# 04_CONNECTOR_IN.net
KiCad netlist of a schematic drawn in Altium Designer
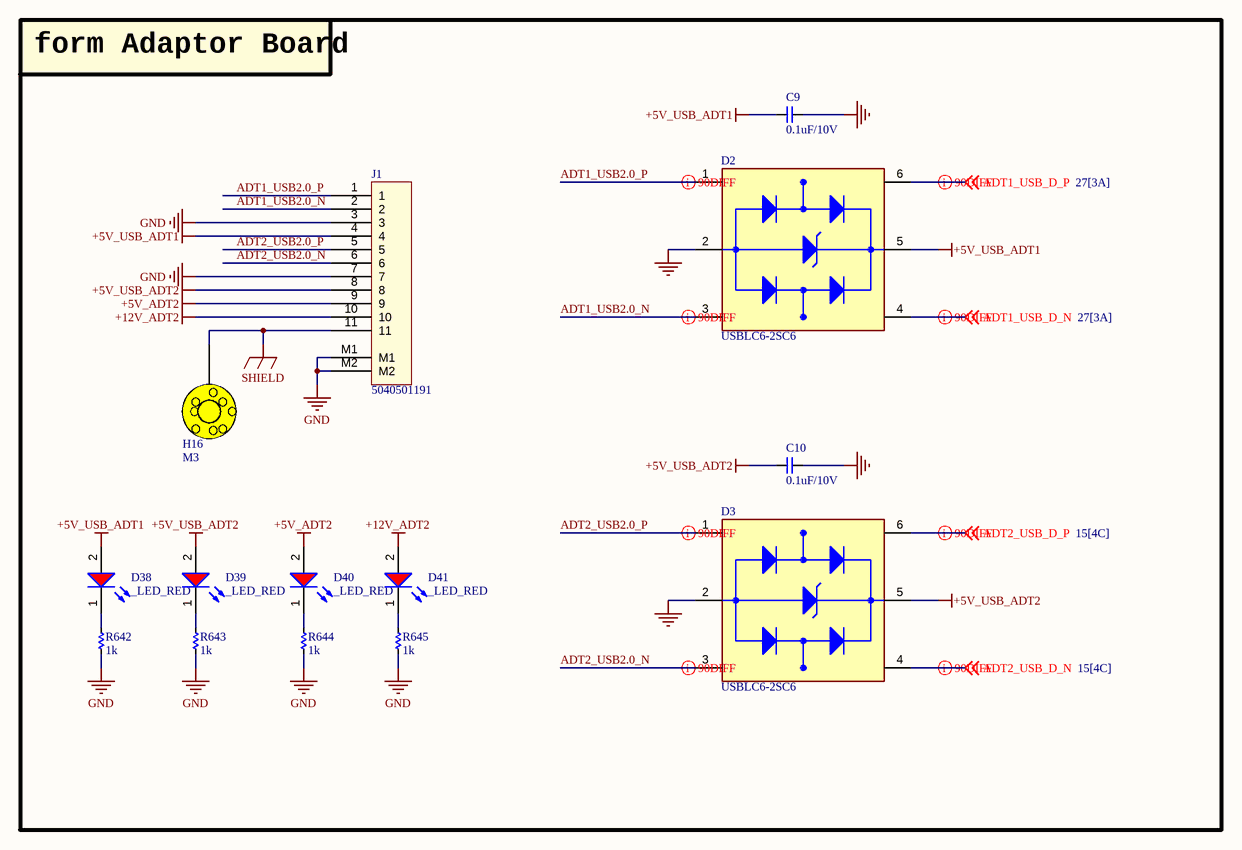
[diagram p0: 04_CONNECTOR_IN.SchDoc]

(export (version "E")
  (design (tool "Eeschema 10.0.6"))
  (components
    (comp (ref "C9")
      (value "0.1uF/10V")
      (footprint "CAP_C_1005X60")
      (description "CAP CHIP")
      (libsource (lib "LABLIB") (part "_CAP_C_2"))
    )
    (comp (ref "C10")
      (value "0.1uF/10V")
      (footprint "CAP_C_1005X60")
      (description "CAP CHIP")
      (libsource (lib "LABLIB") (part "_CAP_C_2"))
    )
    (comp (ref "D2")
      (value "USBLC6-2SC6")
      (footprint "SOT95P280X145-6N")
      (description "17V Clamp 5A (8/20Âµs) Ipp Tvs Diode Surface Mount SOT-23-6")
      (fields (field (name "MF") "STMicroelectronics"))
      (libsource (lib "USBLC6-2SC6") (part "USBLC6-2SC6"))
    )
    (comp (ref "D3")
      (value "USBLC6-2SC6")
      (footprint "SOT95P280X145-6N")
      (description "17V Clamp 5A (8/20Âµs) Ipp Tvs Diode Surface Mount SOT-23-6")
      (fields (field (name "MF") "STMicroelectronics"))
      (libsource (lib "USBLC6-2SC6") (part "USBLC6-2SC6"))
    )
    (comp (ref "D38") (value "_LED_RED") (footprint "LED_0603") (libsource (lib "LABLIB") (part "_LED_RED")))
    (comp (ref "D39") (value "_LED_RED") (footprint "LED_0603") (libsource (lib "LABLIB") (part "_LED_RED")))
    (comp (ref "D40") (value "_LED_RED") (footprint "LED_0603") (libsource (lib "LABLIB") (part "_LED_RED")))
    (comp (ref "D41") (value "_LED_RED") (footprint "LED_0603") (libsource (lib "LABLIB") (part "_LED_RED")))
    (comp (ref "H16")
      (value "M3")
      (footprint "Testpoint_TH_D350H250")
      (libsource (lib "hex_M3") (part "HEX-M3"))
    )
    (comp (ref "J1")
      (value "5040501191")
      (footprint "MOLEX_5040501191")
      (libsource (lib "LABLIB") (part "Header 11x1_2M"))
    )
    (comp (ref "R642")
      (value "1k")
      (footprint "RES_C_1005X40")
      (description "RES")
      (libsource (lib "LABLIB") (part "_RES_B_2"))
    )
    (comp (ref "R643")
      (value "1k")
      (footprint "RES_C_1005X40")
      (description "RES")
      (libsource (lib "LABLIB") (part "_RES_B_2"))
    )
    (comp (ref "R644")
      (value "1k")
      (footprint "RES_C_1005X40")
      (description "RES")
      (libsource (lib "LABLIB") (part "_RES_B_2"))
    )
    (comp (ref "R645")
      (value "1k")
      (footprint "RES_C_1005X40")
      (description "RES")
      (libsource (lib "LABLIB") (part "_RES_B_2"))
    )
  )
  (nets
    (net (code "1") (name "+5V_ADT2") (class "Default")
      (node (ref "D40") (pin "2") (pinfunction "A_2") (pintype "passive"))
      (node (ref "J1") (pin "9") (pinfunction "9_9") (pintype "passive"))
    )
    (net (code "2") (name "+5V_USB_ADT1") (class "Default")
      (node (ref "C9") (pin "2") (pinfunction "2_2") (pintype "passive"))
      (node (ref "D2") (pin "5") (pinfunction "VBUS_5") (pintype "power_in"))
      (node (ref "D38") (pin "2") (pinfunction "A_2") (pintype "passive"))
      (node (ref "J1") (pin "4") (pinfunction "4_4") (pintype "passive"))
    )
    (net (code "3") (name "+5V_USB_ADT2") (class "Default")
      (node (ref "C10") (pin "2") (pinfunction "2_2") (pintype "passive"))
      (node (ref "D3") (pin "5") (pinfunction "VBUS_5") (pintype "power_in"))
      (node (ref "D39") (pin "2") (pinfunction "A_2") (pintype "passive"))
      (node (ref "J1") (pin "8") (pinfunction "8_8") (pintype "passive"))
    )
    (net (code "4") (name "+12V_ADT2") (class "Default")
      (node (ref "D41") (pin "2") (pinfunction "A_2") (pintype "passive"))
      (node (ref "J1") (pin "10") (pinfunction "10_10") (pintype "passive"))
    )
    (net (code "5") (name "/ADT1_USB2.0_N") (class "Default")
      (node (ref "D2") (pin "3") (pinfunction "I/O2_IN_3") (pintype "passive"))
      (node (ref "J1") (pin "2") (pinfunction "2_2") (pintype "passive"))
    )
    (net (code "6") (name "/ADT1_USB2.0_P") (class "Default")
      (node (ref "D2") (pin "1") (pinfunction "I/O1_IN_1") (pintype "passive"))
      (node (ref "J1") (pin "1") (pinfunction "1_1") (pintype "passive"))
    )
    (net (code "7") (name "/ADT2_USB2.0_N") (class "Default")
      (node (ref "D3") (pin "3") (pinfunction "I/O2_IN_3") (pintype "passive"))
      (node (ref "J1") (pin "6") (pinfunction "6_6") (pintype "passive"))
    )
    (net (code "8") (name "/ADT2_USB2.0_P") (class "Default")
      (node (ref "D3") (pin "1") (pinfunction "I/O1_IN_1") (pintype "passive"))
      (node (ref "J1") (pin "5") (pinfunction "5_5") (pintype "passive"))
    )
    (net (code "9") (name "ADT1_USB_D_N") (class "Default")
      (node (ref "D2") (pin "4") (pinfunction "I/O2_OUT_4") (pintype "passive"))
    )
    (net (code "10") (name "ADT1_USB_D_P") (class "Default")
      (node (ref "D2") (pin "6") (pinfunction "I/O1_OUT_6") (pintype "passive"))
    )
    (net (code "11") (name "ADT2_USB_D_N") (class "Default")
      (node (ref "D3") (pin "4") (pinfunction "I/O2_OUT_4") (pintype "passive"))
    )
    (net (code "12") (name "ADT2_USB_D_P") (class "Default")
      (node (ref "D3") (pin "6") (pinfunction "I/O1_OUT_6") (pintype "passive"))
    )
    (net (code "13") (name "GND") (class "Default")
      (node (ref "C10") (pin "1") (pinfunction "1_1") (pintype "passive"))
      (node (ref "C9") (pin "1") (pinfunction "1_1") (pintype "passive"))
      (node (ref "D2") (pin "2") (pinfunction "GND_2") (pintype "power_in"))
      (node (ref "D3") (pin "2") (pinfunction "GND_2") (pintype "power_in"))
      (node (ref "J1") (pin "3") (pinfunction "3_3") (pintype "passive"))
      (node (ref "J1") (pin "7") (pinfunction "7_7") (pintype "passive"))
      (node (ref "J1") (pin "M1") (pinfunction "M1_M1") (pintype "passive"))
      (node (ref "J1") (pin "M2") (pinfunction "M2_M2") (pintype "passive"))
      (node (ref "R642") (pin "1") (pinfunction "1_1") (pintype "passive"))
      (node (ref "R643") (pin "1") (pinfunction "1_1") (pintype "passive"))
      (node (ref "R644") (pin "1") (pinfunction "1_1") (pintype "passive"))
      (node (ref "R645") (pin "1") (pinfunction "1_1") (pintype "passive"))
    )
    (net (code "14") (name "Net-(D38-K)") (class "Default")
      (node (ref "D38") (pin "1") (pinfunction "K_1") (pintype "passive"))
      (node (ref "R642") (pin "2") (pinfunction "2_2") (pintype "passive"))
    )
    (net (code "15") (name "Net-(D39-K)") (class "Default")
      (node (ref "D39") (pin "1") (pinfunction "K_1") (pintype "passive"))
      (node (ref "R643") (pin "2") (pinfunction "2_2") (pintype "passive"))
    )
    (net (code "16") (name "Net-(D40-K)") (class "Default")
      (node (ref "D40") (pin "1") (pinfunction "K_1") (pintype "passive"))
      (node (ref "R644") (pin "2") (pinfunction "2_2") (pintype "passive"))
    )
    (net (code "17") (name "Net-(D41-K)") (class "Default")
      (node (ref "D41") (pin "1") (pinfunction "K_1") (pintype "passive"))
      (node (ref "R645") (pin "2") (pinfunction "2_2") (pintype "passive"))
    )
    (net (code "18") (name "SHIELD") (class "Default")
      (node (ref "H16") (pin "1") (pinfunction "1_1") (pintype "power_in"))
      (node (ref "J1") (pin "11") (pinfunction "11_11") (pintype "passive"))
    )
  )
)
